# Grove_-_LED_String_Light.net
KiCad netlist of a schematic drawn in EAGLE
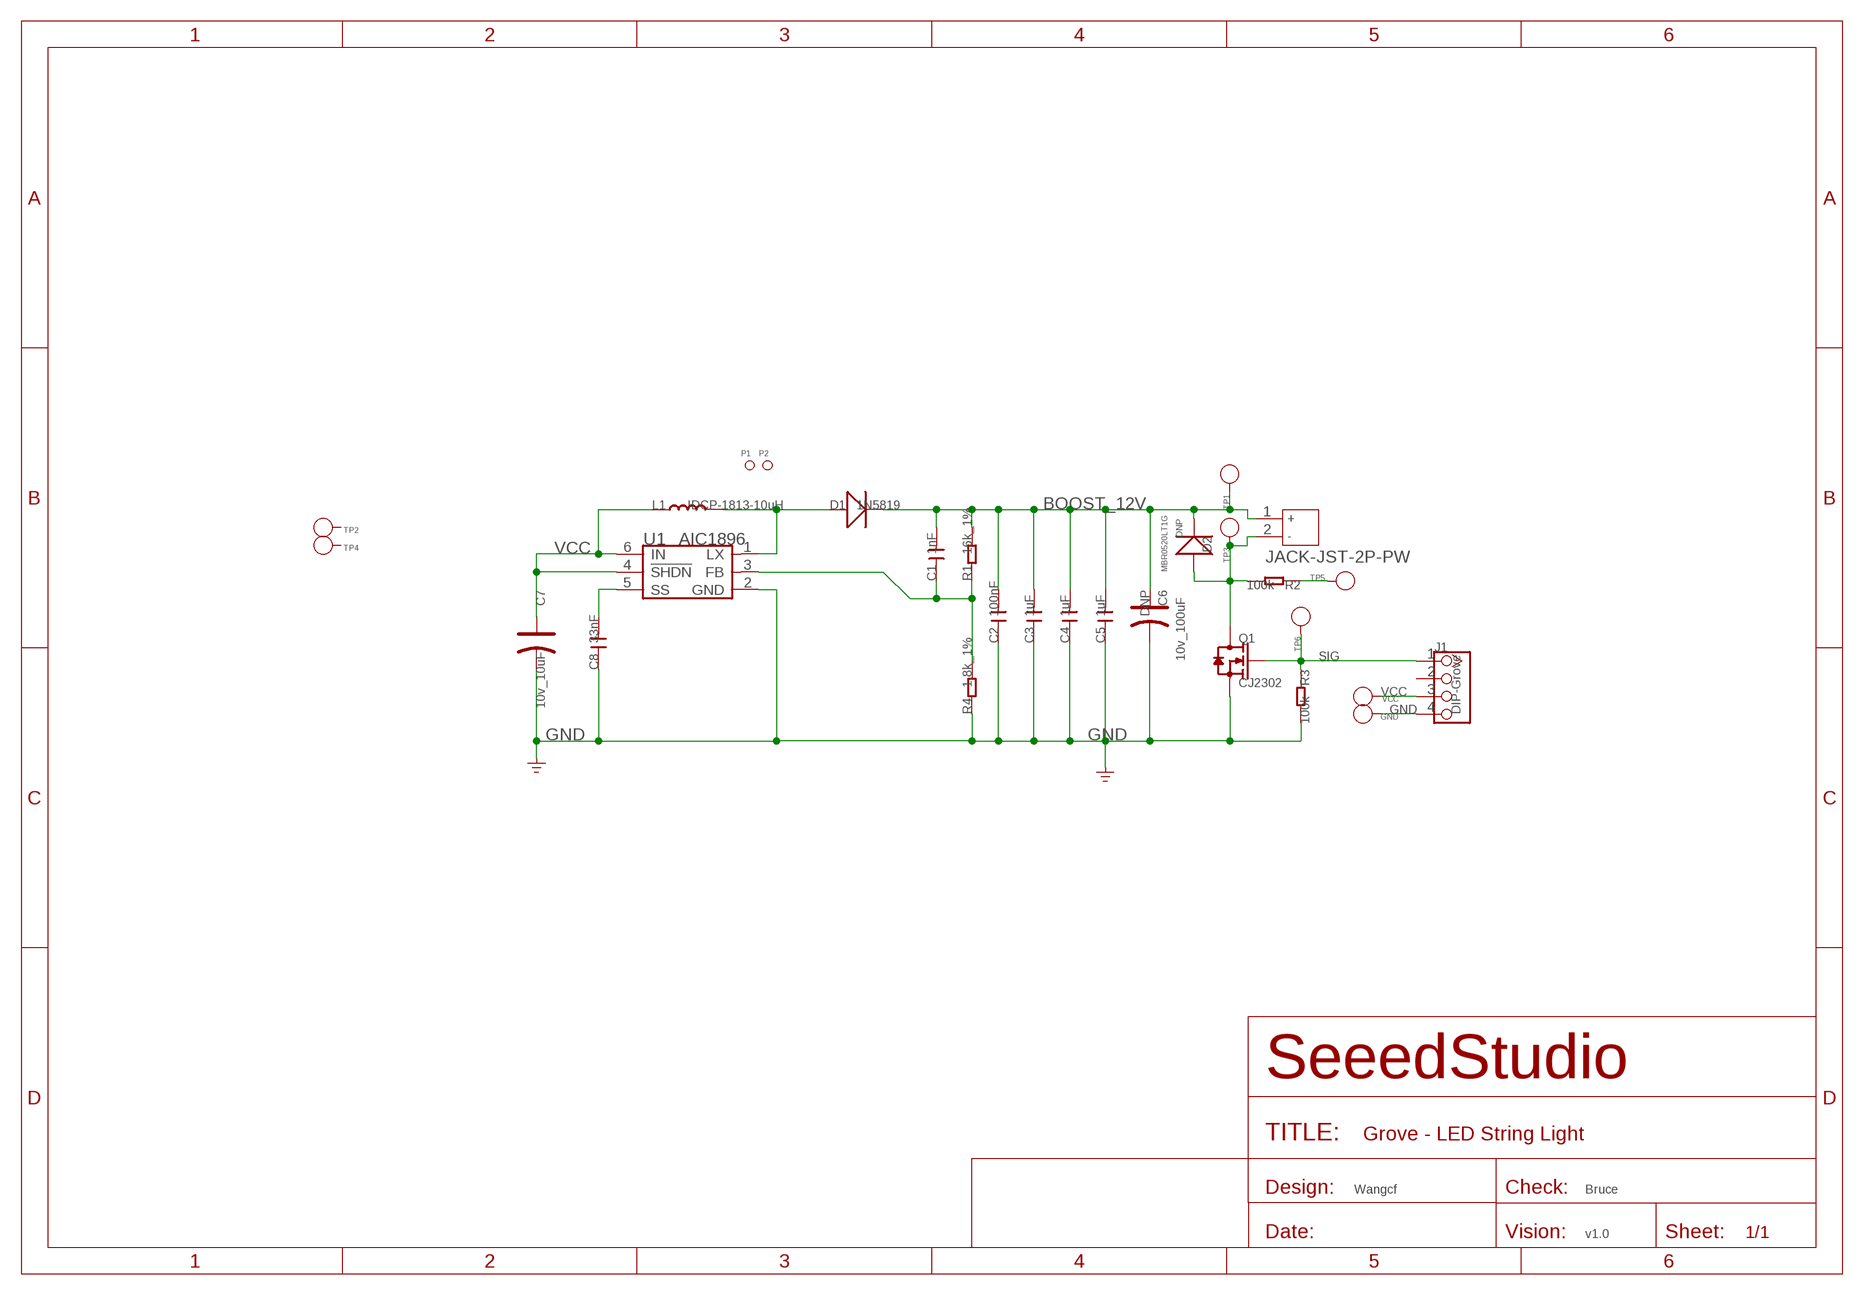
[diagram p0: schematic, sheet 1]

(export (version "E")
  (design (tool "Eeschema 10.0.6"))
  (components
    (comp (ref "C1")
      (value "1nF")
      (footprint "eagle-import:C0603")
      (libsource (lib "eagle-import") (part "C-0603"))
    )
    (comp (ref "C2")
      (value "100nF")
      (footprint "eagle-import:C0603")
      (libsource (lib "eagle-import") (part "C-0603"))
    )
    (comp (ref "C3")
      (value "1uF")
      (footprint "eagle-import:C0603")
      (libsource (lib "eagle-import") (part "C-0603"))
    )
    (comp (ref "C4")
      (value "1uF")
      (footprint "eagle-import:C0603")
      (libsource (lib "eagle-import") (part "C-0603"))
    )
    (comp (ref "C5")
      (value "1uF")
      (footprint "eagle-import:C0603")
      (libsource (lib "eagle-import") (part "C-0603"))
    )
    (comp (ref "C6")
      (value "DNP")
      (footprint "eagle-import:AVX_C")
      (libsource (lib "eagle-import") (part "006-CAP_AVX_C"))
    )
    (comp (ref "C7")
      (value "10v_10uF")
      (footprint "eagle-import:AVX-A")
      (libsource (lib "eagle-import") (part "CAP-AVX-A"))
    )
    (comp (ref "C8")
      (value "33nF")
      (footprint "eagle-import:C0603")
      (libsource (lib "eagle-import") (part "C-0603"))
    )
    (comp (ref "D1")
      (value "1N5819")
      (footprint "eagle-import:D2010")
      (libsource (lib "eagle-import") (part "D'SMA'"))
    )
    (comp (ref "D2")
      (value "DNP")
      (footprint "eagle-import:SOD123")
      (libsource (lib "eagle-import") (part "D'1206'"))
    )
    (comp (ref "GND")
      (value "PAD-TEST-POINT'4545'")
      (footprint "eagle-import:TP_4545")
      (fields (field (name "PARTNO") "DNP"))
      (libsource (lib "eagle-import") (part "PAD-TEST-POINT'4545'"))
    )
    (comp (ref "J1")
      (value "DIP-Grove")
      (footprint "eagle-import:4P-2.0")
      (libsource (lib "eagle-import") (part "TWIG-4P-2.0-2.0"))
    )
    (comp (ref "J3")
      (value "JACK-JST-2P-PW")
      (footprint "eagle-import:JST-2.0")
      (libsource (lib "eagle-import") (part "JACK-JST-2P-PW'2.0'"))
    )
    (comp (ref "L1")
      (value "IDCP-1813-10uH")
      (footprint "eagle-import:1813@1")
      (libsource (lib "eagle-import") (part "013-L1813"))
    )
    (comp (ref "P1")
      (value "PAD-MARK")
      (footprint "eagle-import:ROUND-MARK-1.0")
      (fields (field (name "PARTNO") "DNP"))
      (libsource (lib "eagle-import") (part "PAD-MARK"))
    )
    (comp (ref "P2")
      (value "PAD-MARK")
      (footprint "eagle-import:ROUND-MARK-1.0")
      (fields (field (name "PARTNO") "DNP"))
      (libsource (lib "eagle-import") (part "PAD-MARK"))
    )
    (comp (ref "Q1")
      (value "CJ2302")
      (footprint "eagle-import:SOT23")
      (libsource (lib "eagle-import") (part "MOSFET-N'SOT23'"))
    )
    (comp (ref "R1")
      (value "16k_1%")
      (footprint "eagle-import:R0603")
      (libsource (lib "eagle-import") (part "R-0603"))
    )
    (comp (ref "R2")
      (value "100k")
      (footprint "eagle-import:R0603")
      (libsource (lib "eagle-import") (part "R-0603"))
    )
    (comp (ref "R3")
      (value "100k")
      (footprint "eagle-import:R0603")
      (libsource (lib "eagle-import") (part "R-0603"))
    )
    (comp (ref "R4")
      (value "1.8k_1%")
      (footprint "eagle-import:R0603")
      (libsource (lib "eagle-import") (part "R-0603"))
    )
    (comp (ref "TP1")
      (value "PAD-TEST-POINT'4545'")
      (footprint "eagle-import:TP_4545")
      (fields (field (name "PARTNO") "DNP"))
      (libsource (lib "eagle-import") (part "PAD-TEST-POINT'4545'"))
    )
    (comp (ref "TP2")
      (value "PAD-TEST-POINT'4545'")
      (footprint "eagle-import:TP_4545")
      (fields (field (name "PARTNO") "DNP"))
      (libsource (lib "eagle-import") (part "PAD-TEST-POINT'4545'"))
    )
    (comp (ref "TP3")
      (value "PAD-TEST-POINT'4545'")
      (footprint "eagle-import:TP_4545")
      (fields (field (name "PARTNO") "DNP"))
      (libsource (lib "eagle-import") (part "PAD-TEST-POINT'4545'"))
    )
    (comp (ref "TP4")
      (value "PAD-TEST-POINT'4545'")
      (footprint "eagle-import:TP_4545")
      (fields (field (name "PARTNO") "DNP"))
      (libsource (lib "eagle-import") (part "PAD-TEST-POINT'4545'"))
    )
    (comp (ref "TP5")
      (value "PAD-TEST-POINT'4545'")
      (footprint "eagle-import:TP_4545")
      (fields (field (name "PARTNO") "DNP"))
      (libsource (lib "eagle-import") (part "PAD-TEST-POINT'4545'"))
    )
    (comp (ref "TP6")
      (value "PAD-TEST-POINT'4545'")
      (footprint "eagle-import:TP_4545")
      (fields (field (name "PARTNO") "DNP"))
      (libsource (lib "eagle-import") (part "PAD-TEST-POINT'4545'"))
    )
    (comp (ref "U1")
      (value "AIC1896")
      (footprint "eagle-import:SOT23-6")
      (libsource (lib "eagle-import") (part "AIC1896"))
    )
    (comp (ref "VCC")
      (value "PAD-TEST-POINT'4545'")
      (footprint "eagle-import:TP_4545")
      (fields (field (name "PARTNO") "DNP"))
      (libsource (lib "eagle-import") (part "PAD-TEST-POINT'4545'"))
    )
  )
  (nets
    (net (code "1") (name "/BOOST_12V") (class "Default")
      (node (ref "C1") (pin "2") (pinfunction "2_2") (pintype "passive"))
      (node (ref "C2") (pin "2") (pinfunction "2_2") (pintype "passive"))
      (node (ref "C3") (pin "2") (pinfunction "2_2") (pintype "passive"))
      (node (ref "C4") (pin "2") (pinfunction "2_2") (pintype "passive"))
      (node (ref "C5") (pin "2") (pinfunction "2_2") (pintype "passive"))
      (node (ref "C6") (pin "+") (pinfunction "+_+") (pintype "passive"))
      (node (ref "D1") (pin "-") (pinfunction "-_-") (pintype "passive"))
      (node (ref "D2") (pin "-") (pinfunction "-_-") (pintype "passive"))
      (node (ref "J3") (pin "1") (pinfunction "P$1_1") (pintype "bidirectional"))
      (node (ref "R1") (pin "2") (pinfunction "2_2") (pintype "passive"))
      (node (ref "TP1") (pin "T") (pinfunction "T_T") (pintype "bidirectional"))
    )
    (net (code "2") (name "/SIG") (class "Default")
      (node (ref "J1") (pin "1") (pinfunction "1_1") (pintype "bidirectional"))
      (node (ref "Q1") (pin "1") (pinfunction "G_1") (pintype "passive"))
      (node (ref "R3") (pin "1") (pinfunction "1_1") (pintype "passive"))
      (node (ref "TP6") (pin "T") (pinfunction "T_T") (pintype "bidirectional"))
    )
    (net (code "3") (name "/VCC") (class "Default")
      (node (ref "C7") (pin "+") (pinfunction "+_+") (pintype "passive"))
      (node (ref "J1") (pin "3") (pinfunction "3_3") (pintype "bidirectional"))
      (node (ref "L1") (pin "1") (pinfunction "1_1") (pintype "passive"))
      (node (ref "U1") (pin "4") (pinfunction "~{SHDN}_4") (pintype "input"))
      (node (ref "U1") (pin "6") (pinfunction "IN_6") (pintype "input"))
      (node (ref "VCC") (pin "T") (pinfunction "T_T") (pintype "bidirectional"))
    )
    (net (code "4") (name "GND_POWER") (class "Default")
      (node (ref "C2") (pin "1") (pinfunction "1_1") (pintype "passive"))
      (node (ref "C3") (pin "1") (pinfunction "1_1") (pintype "passive"))
      (node (ref "C4") (pin "1") (pinfunction "1_1") (pintype "passive"))
      (node (ref "C5") (pin "1") (pinfunction "1_1") (pintype "passive"))
      (node (ref "C6") (pin "-") (pinfunction "-_-") (pintype "passive"))
      (node (ref "C7") (pin "-") (pinfunction "-_-") (pintype "passive"))
      (node (ref "C8") (pin "1") (pinfunction "1_1") (pintype "passive"))
      (node (ref "GND") (pin "T") (pinfunction "T_T") (pintype "bidirectional"))
      (node (ref "J1") (pin "4") (pinfunction "4_4") (pintype "bidirectional"))
      (node (ref "Q1") (pin "2") (pinfunction "S_2") (pintype "passive"))
      (node (ref "R3") (pin "2") (pinfunction "2_2") (pintype "passive"))
      (node (ref "R4") (pin "1") (pinfunction "1_1") (pintype "passive"))
      (node (ref "U1") (pin "2") (pinfunction "GND_2") (pintype "power_in"))
    )
    (net (code "5") (name "Net-(J3-P$2)") (class "Default")
      (node (ref "D2") (pin "+") (pinfunction "+_+") (pintype "passive"))
      (node (ref "J3") (pin "2") (pinfunction "P$2_2") (pintype "bidirectional"))
      (node (ref "Q1") (pin "3") (pinfunction "D_3") (pintype "passive"))
      (node (ref "R2") (pin "2") (pinfunction "2_2") (pintype "passive"))
      (node (ref "TP3") (pin "T") (pinfunction "T_T") (pintype "bidirectional"))
    )
    (net (code "6") (name "Net-(R2-Pad1)") (class "Default")
      (node (ref "R2") (pin "1") (pinfunction "1_1") (pintype "passive"))
      (node (ref "TP5") (pin "T") (pinfunction "T_T") (pintype "bidirectional"))
    )
    (net (code "7") (name "Net-(U1-FB)") (class "Default")
      (node (ref "C1") (pin "1") (pinfunction "1_1") (pintype "passive"))
      (node (ref "R1") (pin "1") (pinfunction "1_1") (pintype "passive"))
      (node (ref "R4") (pin "2") (pinfunction "2_2") (pintype "passive"))
      (node (ref "U1") (pin "3") (pinfunction "FB_3") (pintype "input"))
    )
    (net (code "8") (name "Net-(U1-LX)") (class "Default")
      (node (ref "D1") (pin "+") (pinfunction "+_+") (pintype "passive"))
      (node (ref "L1") (pin "2") (pinfunction "2_2") (pintype "passive"))
      (node (ref "U1") (pin "1") (pinfunction "LX_1") (pintype "output"))
    )
    (net (code "9") (name "Net-(U1-SS)") (class "Default")
      (node (ref "C8") (pin "2") (pinfunction "2_2") (pintype "passive"))
      (node (ref "U1") (pin "5") (pinfunction "SS_5") (pintype "input"))
    )
    (net (code "10") (name "unconnected-(J1-Pad2)") (class "Default")
      (node (ref "J1") (pin "2") (pinfunction "2_2") (pintype "bidirectional"))
    )
    (net (code "11") (name "unconnected-(TP2-PadT)") (class "Default")
      (node (ref "TP2") (pin "T") (pinfunction "T_T") (pintype "bidirectional"))
    )
    (net (code "12") (name "unconnected-(TP4-PadT)") (class "Default")
      (node (ref "TP4") (pin "T") (pinfunction "T_T") (pintype "bidirectional"))
    )
  )
)
